# msxbreakout_fat.net
KiCad netlist of a schematic drawn in Altium Designer
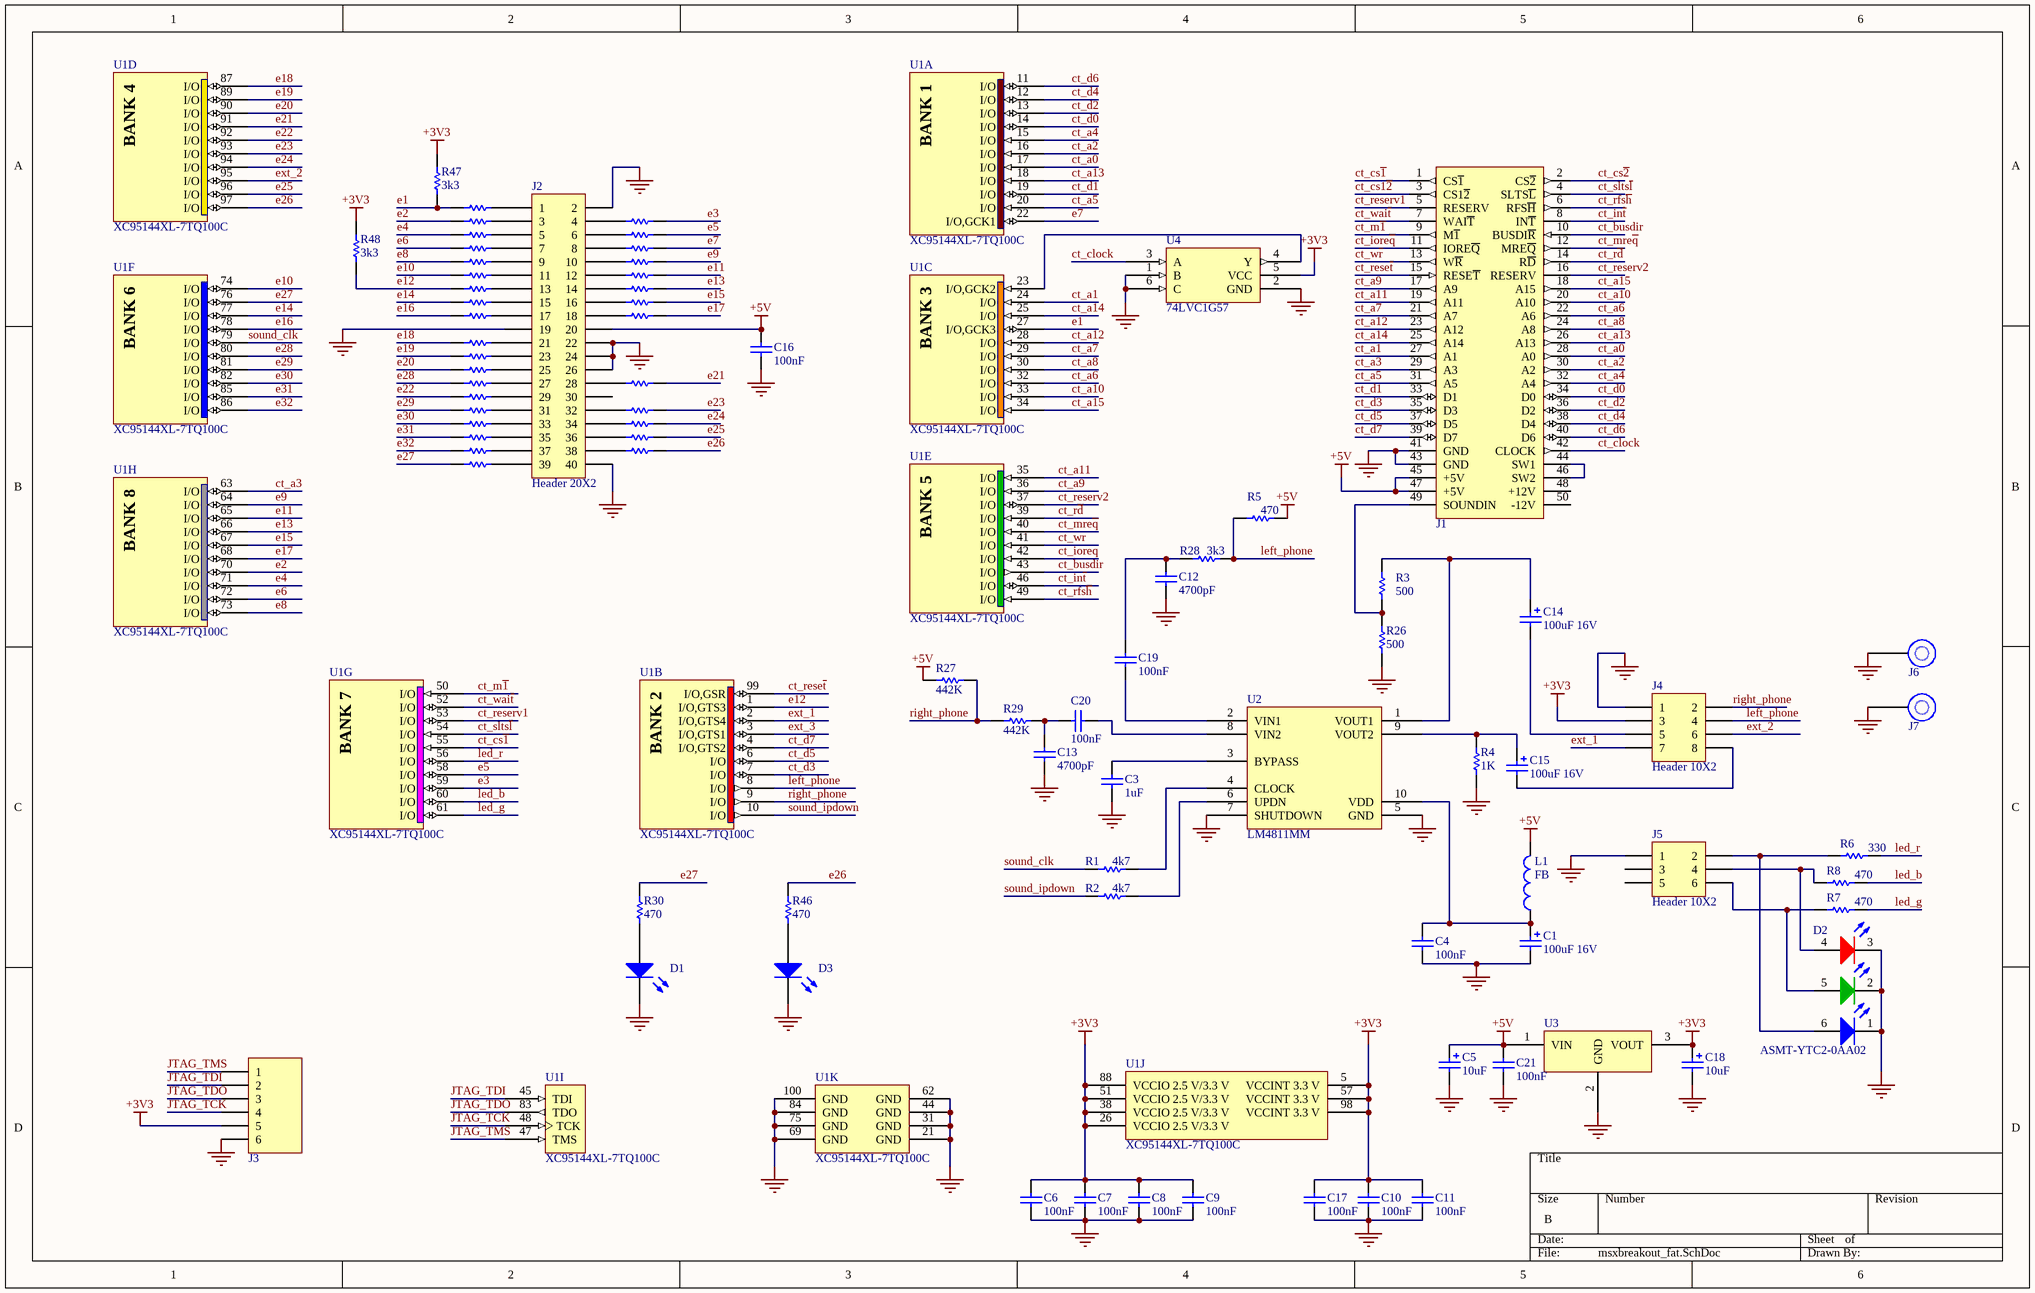
[diagram p0: msxbreakout_fat.SchDoc]

(export (version "E")
  (design (tool "Eeschema 10.0.6"))
  (components
    (comp (ref "C1")
      (value "100uF 16V")
      (footprint "cap1210POL")
      (description "Polarized Capacitor")
      (fields (field (name "Comment") "Cap Pol1") (field (name "PUBLISHER") "Altium Limited"))
      (libsource (lib "altium-import") (part "root_3_Cap Pol1_"))
    )
    (comp (ref "C3")
      (value "1uF")
      (footprint "cap0603")
      (description "Capacitor")
      (fields (field (name "Comment") "Cap") (field (name "PUBLISHER") "Altium Limited"))
      (libsource (lib "altium-import") (part "root_3_Cap_"))
    )
    (comp (ref "C4")
      (value "100nF")
      (footprint "cap0603")
      (description "Capacitor")
      (fields (field (name "Comment") "Cap") (field (name "PUBLISHER") "Altium Limited"))
      (libsource (lib "altium-import") (part "root_1_Cap_"))
    )
    (comp (ref "C5")
      (value "10uF")
      (footprint "cap1210POL")
      (description "Polarized Capacitor")
      (fields (field (name "Comment") "Cap Pol1") (field (name "PUBLISHER") "Altium Limited"))
      (libsource (lib "altium-import") (part "root_3_Cap Pol1_"))
    )
    (comp (ref "C6")
      (value "100nF")
      (footprint "cap0603")
      (description "Capacitor")
      (fields (field (name "Comment") "Cap") (field (name "PUBLISHER") "Altium Limited"))
      (libsource (lib "altium-import") (part "root_1_Cap_"))
    )
    (comp (ref "C7")
      (value "100nF")
      (footprint "cap0603")
      (description "Capacitor")
      (fields (field (name "Comment") "Cap") (field (name "PUBLISHER") "Altium Limited"))
      (libsource (lib "altium-import") (part "root_1_Cap_"))
    )
    (comp (ref "C8")
      (value "100nF")
      (footprint "cap0603")
      (description "Capacitor")
      (fields (field (name "Comment") "Cap") (field (name "PUBLISHER") "Altium Limited"))
      (libsource (lib "altium-import") (part "root_1_Cap_"))
    )
    (comp (ref "C9")
      (value "100nF")
      (footprint "cap0603")
      (description "Capacitor")
      (fields (field (name "Comment") "Cap") (field (name "PUBLISHER") "Altium Limited"))
      (libsource (lib "altium-import") (part "root_1_Cap_"))
    )
    (comp (ref "C10")
      (value "100nF")
      (footprint "cap0603")
      (description "Capacitor")
      (fields (field (name "Comment") "Cap") (field (name "PUBLISHER") "Altium Limited"))
      (libsource (lib "altium-import") (part "root_1_Cap_"))
    )
    (comp (ref "C11")
      (value "100nF")
      (footprint "cap0603")
      (description "Capacitor")
      (fields (field (name "Comment") "Cap") (field (name "PUBLISHER") "Altium Limited"))
      (libsource (lib "altium-import") (part "root_1_Cap_"))
    )
    (comp (ref "C12")
      (value "4700pF")
      (footprint "cap0603")
      (description "Capacitor")
      (fields (field (name "Comment") "Cap") (field (name "PUBLISHER") "Altium Limited"))
      (libsource (lib "altium-import") (part "root_3_Cap_"))
    )
    (comp (ref "C13")
      (value "4700pF")
      (footprint "cap0603")
      (description "Capacitor")
      (fields (field (name "Comment") "Cap") (field (name "PUBLISHER") "Altium Limited"))
      (libsource (lib "altium-import") (part "root_3_Cap_"))
    )
    (comp (ref "C14")
      (value "100uF 16V")
      (footprint "cap1210POL")
      (description "Polarized Capacitor")
      (fields (field (name "Comment") "Cap Pol1") (field (name "PUBLISHER") "Altium Limited"))
      (libsource (lib "altium-import") (part "root_3_Cap Pol1_"))
    )
    (comp (ref "C15")
      (value "100uF 16V")
      (footprint "cap1210POL")
      (description "Polarized Capacitor")
      (fields (field (name "Comment") "Cap Pol1") (field (name "PUBLISHER") "Altium Limited"))
      (libsource (lib "altium-import") (part "root_3_Cap Pol1_"))
    )
    (comp (ref "C16")
      (value "100nF")
      (footprint "cap0603")
      (description "Capacitor")
      (fields (field (name "Comment") "Cap") (field (name "PUBLISHER") "Altium Limited"))
      (libsource (lib "altium-import") (part "root_1_Cap_"))
    )
    (comp (ref "C17")
      (value "100nF")
      (footprint "cap0603")
      (description "Capacitor")
      (fields (field (name "Comment") "Cap") (field (name "PUBLISHER") "Altium Limited"))
      (libsource (lib "altium-import") (part "root_1_Cap_"))
    )
    (comp (ref "C18")
      (value "10uF")
      (footprint "cap1210POL")
      (description "Polarized Capacitor")
      (fields (field (name "Comment") "Cap Pol1") (field (name "PUBLISHER") "Altium Limited"))
      (libsource (lib "altium-import") (part "root_3_Cap Pol1_"))
    )
    (comp (ref "C19")
      (value "100nF")
      (footprint "cap0603")
      (description "Capacitor")
      (fields (field (name "Comment") "Cap") (field (name "PUBLISHER") "Altium Limited"))
      (libsource (lib "altium-import") (part "root_1_Cap_"))
    )
    (comp (ref "C20")
      (value "100nF")
      (footprint "cap0603")
      (description "Capacitor")
      (fields (field (name "Comment") "Cap") (field (name "PUBLISHER") "Altium Limited"))
      (libsource (lib "altium-import") (part "root_2_Cap_"))
    )
    (comp (ref "C21")
      (value "100nF")
      (footprint "cap0603")
      (description "Capacitor")
      (fields (field (name "Comment") "Cap") (field (name "PUBLISHER") "Altium Limited"))
      (libsource (lib "altium-import") (part "root_1_Cap_"))
    )
    (comp (ref "D1")
      (value "APA1606SURCK")
      (footprint "LED-0603_LAMP_BLUE")
      (description "1.6x0.6mm RIGHT ANGLE SMD CHIP LED LAMP, Hyper Red")
      (libsource (lib "altium-import") (part "root_3_APA1606SURCK_"))
    )
    (comp (ref "D2")
      (value "ASMT-YTC2-0AA02")
      (footprint "ASMT-YTC2-0AA02")
      (description "Typical RED, GREEN, YELLOW, AMBER GaAs LED")
      (fields (field (name "PUBLISHER") "Altium Limited"))
      (libsource (lib "altium-import") (part "root_0_ASMT-YTC2-0AA02_"))
    )
    (comp (ref "D3")
      (value "APA1606SURCK")
      (footprint "LED-0603_LAMP_RED")
      (description "1.6x0.6mm RIGHT ANGLE SMD CHIP LED LAMP, Hyper Red")
      (libsource (lib "altium-import") (part "root_3_APA1606SURCK_"))
    )
    (comp (ref "J1")
      (value "msxcart")
      (footprint "msxcart")
      (libsource (lib "altium-import") (part "root_0_msxcart_"))
    )
    (comp (ref "J2")
      (value "Header 20X2")
      (footprint "HDR2X20_90")
      (description "Header, 40-Pin, Dual row")
      (libsource (lib "altium-import") (part "root_0_Header 20X2_"))
    )
    (comp (ref "J3")
      (value "Header 1X6")
      (footprint "HDR1X6_90")
      (description "Header, 6-Pin, Single row")
      (libsource (lib "msxarm") (part "Header 1X6"))
    )
    (comp (ref "J4")
      (value "Header 10X2")
      (footprint "HDR2X4_90")
      (description "Header, 8 -Pin, Dual row")
      (libsource (lib "altium-import") (part "root_0_Header 4X2_"))
    )
    (comp (ref "J5")
      (value "Header 10X2")
      (footprint "HDR2X3_90")
      (description "Header, 10-Pin, Dual row")
      (libsource (lib "altium-import") (part "root_0_Header 3X2_"))
    )
    (comp (ref "J6")
      (value "MountHole")
      (footprint "MOUNTHOLE")
      (description "Mounting hole")
      (libsource (lib "altium-import") (part "root_0_MountHole_"))
    )
    (comp (ref "J7")
      (value "MountHole")
      (footprint "MOUNTHOLE")
      (description "Mounting hole")
      (libsource (lib "altium-import") (part "root_0_MountHole_"))
    )
    (comp (ref "L1")
      (value "FB")
      (footprint "ind1206")
      (description "Inductor")
      (fields (field (name "PUBLISHER") "Altium Limited"))
      (libsource (lib "altium-import") (part "root_1_Inductor_"))
    )
    (comp (ref "R1")
      (value "4k7")
      (footprint "res0603")
      (description "Resistor")
      (fields (field (name "Comment") "Res1") (field (name "PUBLISHER") "Altium Limited"))
      (libsource (lib "altium-import") (part "root_0_Res1_"))
    )
    (comp (ref "R2")
      (value "4k7")
      (footprint "res0603")
      (description "Resistor")
      (fields (field (name "Comment") "Res1") (field (name "PUBLISHER") "Altium Limited"))
      (libsource (lib "altium-import") (part "root_0_Res1_"))
    )
    (comp (ref "R3")
      (value "500")
      (footprint "res0603")
      (description "Resistor")
      (fields (field (name "Comment") "Res1") (field (name "PUBLISHER") "Altium Limited"))
      (libsource (lib "altium-import") (part "root_1_Res1_"))
    )
    (comp (ref "R4")
      (value "1K")
      (footprint "res0603")
      (description "Resistor")
      (fields (field (name "Comment") "Res1") (field (name "PUBLISHER") "Altium Limited"))
      (libsource (lib "altium-import") (part "root_1_Res1_"))
    )
    (comp (ref "R5")
      (value "470")
      (footprint "res0603")
      (description "Resistor")
      (fields (field (name "Comment") "Res1") (field (name "PUBLISHER") "Altium Limited"))
      (libsource (lib "altium-import") (part "root_0_Res1_"))
    )
    (comp (ref "R6")
      (value "330")
      (footprint "res0603")
      (description "Resistor")
      (fields (field (name "Comment") "Res1") (field (name "PUBLISHER") "Altium Limited"))
      (libsource (lib "altium-import") (part "root_0_Res1_"))
    )
    (comp (ref "R7")
      (value "470")
      (footprint "res0603")
      (description "Resistor")
      (fields (field (name "Comment") "Res1") (field (name "PUBLISHER") "Altium Limited"))
      (libsource (lib "altium-import") (part "root_0_Res1_"))
    )
    (comp (ref "R8")
      (value "470")
      (footprint "res0603")
      (description "Resistor")
      (fields (field (name "Comment") "Res1") (field (name "PUBLISHER") "Altium Limited"))
      (libsource (lib "altium-import") (part "root_0_Res1_"))
    )
    (comp (ref "R9")
      (value "Res1")
      (footprint "res0603")
      (description "Resistor")
      (fields (field (name "PUBLISHER") "Altium Limited"))
      (libsource (lib "altium-import") (part "root_0_Res1_"))
    )
    (comp (ref "R10")
      (value "Res1")
      (footprint "res0603")
      (description "Resistor")
      (fields (field (name "PUBLISHER") "Altium Limited"))
      (libsource (lib "altium-import") (part "root_0_Res1_"))
    )
    (comp (ref "R11")
      (value "Res1")
      (footprint "res0603")
      (description "Resistor")
      (fields (field (name "PUBLISHER") "Altium Limited"))
      (libsource (lib "altium-import") (part "root_0_Res1_"))
    )
    (comp (ref "R12")
      (value "Res1")
      (footprint "res0603")
      (description "Resistor")
      (fields (field (name "PUBLISHER") "Altium Limited"))
      (libsource (lib "altium-import") (part "root_0_Res1_"))
    )
    (comp (ref "R13")
      (value "Res1")
      (footprint "res0603")
      (description "Resistor")
      (fields (field (name "PUBLISHER") "Altium Limited"))
      (libsource (lib "altium-import") (part "root_0_Res1_"))
    )
    (comp (ref "R14")
      (value "Res1")
      (footprint "res0603")
      (description "Resistor")
      (fields (field (name "PUBLISHER") "Altium Limited"))
      (libsource (lib "altium-import") (part "root_0_Res1_"))
    )
    (comp (ref "R15")
      (value "Res1")
      (footprint "res0603")
      (description "Resistor")
      (fields (field (name "PUBLISHER") "Altium Limited"))
      (libsource (lib "altium-import") (part "root_0_Res1_"))
    )
    (comp (ref "R16")
      (value "Res1")
      (footprint "res0603")
      (description "Resistor")
      (fields (field (name "PUBLISHER") "Altium Limited"))
      (libsource (lib "altium-import") (part "root_0_Res1_"))
    )
    (comp (ref "R17")
      (value "Res1")
      (footprint "res0603")
      (description "Resistor")
      (fields (field (name "PUBLISHER") "Altium Limited"))
      (libsource (lib "altium-import") (part "root_0_Res1_"))
    )
    (comp (ref "R18")
      (value "Res1")
      (footprint "res0603")
      (description "Resistor")
      (fields (field (name "PUBLISHER") "Altium Limited"))
      (libsource (lib "altium-import") (part "root_0_Res1_"))
    )
    (comp (ref "R19")
      (value "Res1")
      (footprint "res0603")
      (description "Resistor")
      (fields (field (name "PUBLISHER") "Altium Limited"))
      (libsource (lib "altium-import") (part "root_0_Res1_"))
    )
    (comp (ref "R20")
      (value "Res1")
      (footprint "res0603")
      (description "Resistor")
      (fields (field (name "PUBLISHER") "Altium Limited"))
      (libsource (lib "altium-import") (part "root_0_Res1_"))
    )
    (comp (ref "R21")
      (value "Res1")
      (footprint "res0603")
      (description "Resistor")
      (fields (field (name "PUBLISHER") "Altium Limited"))
      (libsource (lib "altium-import") (part "root_0_Res1_"))
    )
    (comp (ref "R22")
      (value "Res1")
      (footprint "res0603")
      (description "Resistor")
      (fields (field (name "PUBLISHER") "Altium Limited"))
      (libsource (lib "altium-import") (part "root_0_Res1_"))
    )
    (comp (ref "R23")
      (value "Res1")
      (footprint "res0603")
      (description "Resistor")
      (fields (field (name "PUBLISHER") "Altium Limited"))
      (libsource (lib "altium-import") (part "root_0_Res1_"))
    )
    (comp (ref "R24")
      (value "Res1")
      (footprint "res0603")
      (description "Resistor")
      (fields (field (name "PUBLISHER") "Altium Limited"))
      (libsource (lib "altium-import") (part "root_0_Res1_"))
    )
    (comp (ref "R25")
      (value "Res1")
      (footprint "res0603")
      (description "Resistor")
      (fields (field (name "PUBLISHER") "Altium Limited"))
      (libsource (lib "altium-import") (part "root_0_Res1_"))
    )
    (comp (ref "R26")
      (value "500")
      (footprint "res0603")
      (description "Resistor")
      (fields (field (name "Comment") "Res1") (field (name "PUBLISHER") "Altium Limited"))
      (libsource (lib "altium-import") (part "root_1_Res1_"))
    )
    (comp (ref "R27")
      (value "442K")
      (footprint "res0603")
      (description "Resistor")
      (fields (field (name "PUBLISHER") "Altium Limited"))
      (libsource (lib "altium-import") (part "root_0_Resistor_"))
    )
    (comp (ref "R28")
      (value "3k3")
      (footprint "res0603")
      (description "Resistor")
      (fields (field (name "Comment") "Res1") (field (name "PUBLISHER") "Altium Limited"))
      (libsource (lib "altium-import") (part "root_0_Res1_"))
    )
    (comp (ref "R29")
      (value "442K")
      (footprint "res0603")
      (description "Resistor")
      (fields (field (name "PUBLISHER") "Altium Limited"))
      (libsource (lib "altium-import") (part "root_0_Resistor_"))
    )
    (comp (ref "R30")
      (value "470")
      (footprint "res0603")
      (description "Resistor")
      (fields (field (name "Comment") "Res1") (field (name "PUBLISHER") "Altium Limited"))
      (libsource (lib "altium-import") (part "root_1_Res1_"))
    )
    (comp (ref "R31")
      (value "Res1")
      (footprint "res0603")
      (description "Resistor")
      (fields (field (name "PUBLISHER") "Altium Limited"))
      (libsource (lib "altium-import") (part "root_0_Res1_"))
    )
    (comp (ref "R32")
      (value "Res1")
      (footprint "res0603")
      (description "Resistor")
      (fields (field (name "PUBLISHER") "Altium Limited"))
      (libsource (lib "altium-import") (part "root_0_Res1_"))
    )
    (comp (ref "R33")
      (value "Res1")
      (footprint "res0603")
      (description "Resistor")
      (fields (field (name "PUBLISHER") "Altium Limited"))
      (libsource (lib "altium-import") (part "root_0_Res1_"))
    )
    (comp (ref "R34")
      (value "Res1")
      (footprint "res0603")
      (description "Resistor")
      (fields (field (name "PUBLISHER") "Altium Limited"))
      (libsource (lib "altium-import") (part "root_0_Res1_"))
    )
    (comp (ref "R35")
      (value "Res1")
      (footprint "res0603")
      (description "Resistor")
      (fields (field (name "PUBLISHER") "Altium Limited"))
      (libsource (lib "altium-import") (part "root_0_Res1_"))
    )
    (comp (ref "R36")
      (value "Res1")
      (footprint "res0603")
      (description "Resistor")
      (fields (field (name "PUBLISHER") "Altium Limited"))
      (libsource (lib "altium-import") (part "root_0_Res1_"))
    )
    (comp (ref "R37")
      (value "Res1")
      (footprint "res0603")
      (description "Resistor")
      (fields (field (name "PUBLISHER") "Altium Limited"))
      (libsource (lib "altium-import") (part "root_0_Res1_"))
    )
    (comp (ref "R38")
      (value "Res1")
      (footprint "res0603")
      (description "Resistor")
      (fields (field (name "PUBLISHER") "Altium Limited"))
      (libsource (lib "altium-import") (part "root_0_Res1_"))
    )
    (comp (ref "R39")
      (value "Res1")
      (footprint "res0603")
      (description "Resistor")
      (fields (field (name "PUBLISHER") "Altium Limited"))
      (libsource (lib "altium-import") (part "root_0_Res1_"))
    )
    (comp (ref "R40")
      (value "Res1")
      (footprint "res0603")
      (description "Resistor")
      (fields (field (name "PUBLISHER") "Altium Limited"))
      (libsource (lib "altium-import") (part "root_0_Res1_"))
    )
    (comp (ref "R41")
      (value "Res1")
      (footprint "res0603")
      (description "Resistor")
      (fields (field (name "PUBLISHER") "Altium Limited"))
      (libsource (lib "altium-import") (part "root_0_Res1_"))
    )
    (comp (ref "R42")
      (value "Res1")
      (footprint "res0603")
      (description "Resistor")
      (fields (field (name "PUBLISHER") "Altium Limited"))
      (libsource (lib "altium-import") (part "root_0_Res1_"))
    )
    (comp (ref "R43")
      (value "Res1")
      (footprint "res0603")
      (description "Resistor")
      (fields (field (name "PUBLISHER") "Altium Limited"))
      (libsource (lib "altium-import") (part "root_0_Res1_"))
    )
    (comp (ref "R44")
      (value "Res1")
      (footprint "res0603")
      (description "Resistor")
      (fields (field (name "PUBLISHER") "Altium Limited"))
      (libsource (lib "altium-import") (part "root_0_Res1_"))
    )
    (comp (ref "R45")
      (value "Res1")
      (footprint "res0603")
      (description "Resistor")
      (fields (field (name "PUBLISHER") "Altium Limited"))
      (libsource (lib "altium-import") (part "root_0_Res1_"))
    )
    (comp (ref "R46")
      (value "470")
      (footprint "res0603")
      (description "Resistor")
      (fields (field (name "Comment") "Res1") (field (name "PUBLISHER") "Altium Limited"))
      (libsource (lib "altium-import") (part "root_1_Res1_"))
    )
    (comp (ref "R47")
      (value "3k3")
      (footprint "res0603")
      (description "Resistor")
      (fields (field (name "Comment") "Res1") (field (name "PUBLISHER") "Altium Limited"))
      (libsource (lib "altium-import") (part "root_1_Res1_"))
    )
    (comp (ref "R48")
      (value "3k3")
      (footprint "res0603")
      (description "Resistor")
      (fields (field (name "Comment") "Res1") (field (name "PUBLISHER") "Altium Limited"))
      (libsource (lib "altium-import") (part "root_1_Res1_"))
    )
    (comp (ref "U1")
      (value "XC95144XL-7TQ100C")
      (footprint "TQ100_M")
      (libsource (lib "altium-import") (part "root_0_XC95144XL-7TQ100C_"))
    )
    (comp (ref "U2") (value "LM4811MM") (footprint "LM4811MM") (libsource (lib "msxarm") (part "LM4811MM")))
    (comp (ref "U3")
      (value "Regulator 3V3")
      (footprint "sot223_4")
      (libsource (lib "altium-import") (part "root_0_Regulator 3V3_"))
    )
    (comp (ref "U4")
      (value "74LVC1G57")
      (footprint "SOT-363 PKG")
      (libsource (lib "altium-import") (part "root_0_74LVC1G57_"))
    )
  )
  (nets
    (net (code "1") (name "+3V3") (class "Default")
      (node (ref "C10") (pin "2") (pinfunction "2_2") (pintype "passive"))
      (node (ref "C11") (pin "2") (pinfunction "2_2") (pintype "passive"))
      (node (ref "C17") (pin "2") (pinfunction "2_2") (pintype "passive"))
      (node (ref "C18") (pin "1") (pinfunction "1_1") (pintype "passive"))
      (node (ref "C6") (pin "2") (pinfunction "2_2") (pintype "passive"))
      (node (ref "C7") (pin "2") (pinfunction "2_2") (pintype "passive"))
      (node (ref "C8") (pin "2") (pinfunction "2_2") (pintype "passive"))
      (node (ref "C9") (pin "2") (pinfunction "2_2") (pintype "passive"))
      (node (ref "J3") (pin "5") (pinfunction "5_5") (pintype "passive"))
      (node (ref "J4") (pin "3") (pinfunction "3_3") (pintype "passive"))
      (node (ref "R47") (pin "2") (pinfunction "2_2") (pintype "passive"))
      (node (ref "R48") (pin "2") (pinfunction "2_2") (pintype "passive"))
      (node (ref "U1") (pin "26") (pinfunction "VCCIO_2.5_V/3.3_V_26") (pintype "power_in"))
      (node (ref "U1") (pin "38") (pinfunction "VCCIO_2.5_V/3.3_V_38") (pintype "power_in"))
      (node (ref "U1") (pin "5") (pinfunction "VCCINT_3.3_V_5") (pintype "power_in"))
      (node (ref "U1") (pin "51") (pinfunction "VCCIO_2.5_V/3.3_V_51") (pintype "power_in"))
      (node (ref "U1") (pin "57") (pinfunction "VCCINT_3.3_V_57") (pintype "power_in"))
      (node (ref "U1") (pin "88") (pinfunction "VCCIO_2.5_V/3.3_V_88") (pintype "power_in"))
      (node (ref "U1") (pin "98") (pinfunction "VCCINT_3.3_V_98") (pintype "power_in"))
      (node (ref "U3") (pin "3") (pinfunction "VOUT_3") (pintype "passive"))
      (node (ref "U4") (pin "5") (pinfunction "VCC_5") (pintype "power_in"))
    )
    (net (code "2") (name "+5V") (class "Default")
      (node (ref "C16") (pin "2") (pinfunction "2_2") (pintype "passive"))
      (node (ref "C21") (pin "2") (pinfunction "2_2") (pintype "passive"))
      (node (ref "C5") (pin "1") (pinfunction "1_1") (pintype "passive"))
      (node (ref "J1") (pin "45") (pinfunction "+5V_45") (pintype "power_in"))
      (node (ref "J1") (pin "47") (pinfunction "+5V_47") (pintype "power_in"))
      (node (ref "J2") (pin "20") (pinfunction "20_20") (pintype "passive"))
      (node (ref "L1") (pin "2") (pinfunction "2_2") (pintype "passive"))
      (node (ref "R27") (pin "1") (pinfunction "1_1") (pintype "passive"))
      (node (ref "R5") (pin "2") (pinfunction "2_2") (pintype "passive"))
      (node (ref "U3") (pin "1") (pinfunction "VIN_1") (pintype "passive"))
    )
    (net (code "3") (name "/JTAG_TCK") (class "Default")
      (node (ref "J3") (pin "4") (pinfunction "4_4") (pintype "passive"))
      (node (ref "U1") (pin "48") (pinfunction "TCK_48") (pintype "input"))
    )
    (net (code "4") (name "/JTAG_TDI") (class "Default")
      (node (ref "J3") (pin "2") (pinfunction "2_2") (pintype "passive"))
      (node (ref "U1") (pin "45") (pinfunction "TDI_45") (pintype "input"))
    )
    (net (code "5") (name "/JTAG_TDO") (class "Default")
      (node (ref "J3") (pin "3") (pinfunction "3_3") (pintype "passive"))
      (node (ref "U1") (pin "83") (pinfunction "TDO_83") (pintype "output"))
    )
    (net (code "6") (name "/JTAG_TMS") (class "Default")
      (node (ref "J3") (pin "1") (pinfunction "1_1") (pintype "passive"))
      (node (ref "U1") (pin "47") (pinfunction "TMS_47") (pintype "input"))
    )
    (net (code "7") (name "/ct_a0") (class "Default")
      (node (ref "J1") (pin "28") (pinfunction "A0_28") (pintype "output"))
      (node (ref "U1") (pin "17") (pinfunction "I/O_17") (pintype "bidirectional"))
    )
    (net (code "8") (name "/ct_a1") (class "Default")
      (node (ref "J1") (pin "27") (pinfunction "A1_27") (pintype "output"))
      (node (ref "U1") (pin "24") (pinfunction "I/O_24") (pintype "bidirectional"))
    )
    (net (code "9") (name "/ct_a2") (class "Default")
      (node (ref "J1") (pin "30") (pinfunction "A2_30") (pintype "output"))
      (node (ref "U1") (pin "16") (pinfunction "I/O_16") (pintype "bidirectional"))
    )
    (net (code "10") (name "/ct_a3") (class "Default")
      (node (ref "J1") (pin "29") (pinfunction "A3_29") (pintype "output"))
      (node (ref "U1") (pin "63") (pinfunction "I/O_63") (pintype "bidirectional"))
    )
    (net (code "11") (name "/ct_a4") (class "Default")
      (node (ref "J1") (pin "32") (pinfunction "A4_32") (pintype "output"))
      (node (ref "U1") (pin "15") (pinfunction "I/O_15") (pintype "bidirectional"))
    )
    (net (code "12") (name "/ct_a5") (class "Default")
      (node (ref "J1") (pin "31") (pinfunction "A5_31") (pintype "output"))
      (node (ref "U1") (pin "20") (pinfunction "I/O_20") (pintype "bidirectional"))
    )
    (net (code "13") (name "/ct_a6") (class "Default")
      (node (ref "J1") (pin "22") (pinfunction "A6_22") (pintype "output"))
      (node (ref "U1") (pin "32") (pinfunction "I/O_32") (pintype "bidirectional"))
    )
    (net (code "14") (name "/ct_a7") (class "Default")
      (node (ref "J1") (pin "21") (pinfunction "A7_21") (pintype "output"))
      (node (ref "U1") (pin "29") (pinfunction "I/O_29") (pintype "bidirectional"))
    )
    (net (code "15") (name "/ct_a8") (class "Default")
      (node (ref "J1") (pin "24") (pinfunction "A8_24") (pintype "output"))
      (node (ref "U1") (pin "30") (pinfunction "I/O_30") (pintype "bidirectional"))
    )
    (net (code "16") (name "/ct_a9") (class "Default")
      (node (ref "J1") (pin "17") (pinfunction "A9_17") (pintype "output"))
      (node (ref "U1") (pin "36") (pinfunction "I/O_36") (pintype "bidirectional"))
    )
    (net (code "17") (name "/ct_a10") (class "Default")
      (node (ref "J1") (pin "20") (pinfunction "A10_20") (pintype "output"))
      (node (ref "U1") (pin "33") (pinfunction "I/O_33") (pintype "bidirectional"))
    )
    (net (code "18") (name "/ct_a11") (class "Default")
      (node (ref "J1") (pin "19") (pinfunction "A11_19") (pintype "output"))
      (node (ref "U1") (pin "35") (pinfunction "I/O_35") (pintype "bidirectional"))
    )
    (net (code "19") (name "/ct_a12") (class "Default")
      (node (ref "J1") (pin "23") (pinfunction "A12_23") (pintype "output"))
      (node (ref "U1") (pin "28") (pinfunction "I/O_28") (pintype "bidirectional"))
    )
    (net (code "20") (name "/ct_a13") (class "Default")
      (node (ref "J1") (pin "26") (pinfunction "A13_26") (pintype "output"))
      (node (ref "U1") (pin "18") (pinfunction "I/O_18") (pintype "bidirectional"))
    )
    (net (code "21") (name "/ct_a14") (class "Default")
      (node (ref "J1") (pin "25") (pinfunction "A14_25") (pintype "output"))
      (node (ref "U1") (pin "25") (pinfunction "I/O_25") (pintype "bidirectional"))
    )
    (net (code "22") (name "/ct_a15") (class "Default")
      (node (ref "J1") (pin "18") (pinfunction "A15_18") (pintype "output"))
      (node (ref "U1") (pin "34") (pinfunction "I/O_34") (pintype "bidirectional"))
    )
    (net (code "23") (name "/ct_busdir") (class "Default")
      (node (ref "J1") (pin "10") (pinfunction "BUSDI~{R}_10") (pintype "input"))
      (node (ref "U1") (pin "43") (pinfunction "I/O_43") (pintype "bidirectional"))
    )
    (net (code "24") (name "/ct_clock") (class "Default")
      (node (ref "J1") (pin "42") (pinfunction "CLOCK_42") (pintype "output"))
      (node (ref "U4") (pin "3") (pinfunction "A_3") (pintype "input"))
    )
    (net (code "25") (name "/ct_cs1~{2}") (class "Default")
      (node (ref "J1") (pin "3") (pinfunction "CS1~{2}_3") (pintype "output"))
    )
    (net (code "26") (name "/ct_cs~{1}") (class "Default")
      (node (ref "J1") (pin "1") (pinfunction "CS~{1}_1") (pintype "output"))
      (node (ref "U1") (pin "55") (pinfunction "I/O_55") (pintype "bidirectional"))
    )
    (net (code "27") (name "/ct_cs~{2}") (class "Default")
      (node (ref "J1") (pin "2") (pinfunction "CS~{2}_2") (pintype "output"))
    )
    (net (code "28") (name "/ct_d0") (class "Default")
      (node (ref "J1") (pin "34") (pinfunction "D0_34") (pintype "bidirectional"))
      (node (ref "U1") (pin "14") (pinfunction "I/O_14") (pintype "bidirectional"))
    )
    (net (code "29") (name "/ct_d1") (class "Default")
      (node (ref "J1") (pin "33") (pinfunction "D1_33") (pintype "bidirectional"))
      (node (ref "U1") (pin "19") (pinfunction "I/O_19") (pintype "bidirectional"))
    )
    (net (code "30") (name "/ct_d2") (class "Default")
      (node (ref "J1") (pin "36") (pinfunction "D2_36") (pintype "bidirectional"))
      (node (ref "U1") (pin "13") (pinfunction "I/O_13") (pintype "bidirectional"))
    )
    (net (code "31") (name "/ct_d3") (class "Default")
      (node (ref "J1") (pin "35") (pinfunction "D3_35") (pintype "bidirectional"))
      (node (ref "U1") (pin "7") (pinfunction "I/O_7") (pintype "bidirectional"))
    )
    (net (code "32") (name "/ct_d4") (class "Default")
      (node (ref "J1") (pin "38") (pinfunction "D4_38") (pintype "bidirectional"))
      (node (ref "U1") (pin "12") (pinfunction "I/O_12") (pintype "bidirectional"))
    )
    (net (code "33") (name "/ct_d5") (class "Default")
      (node (ref "J1") (pin "37") (pinfunction "D5_37") (pintype "bidirectional"))
      (node (ref "U1") (pin "6") (pinfunction "I/O_6") (pintype "bidirectional"))
    )
    (net (code "34") (name "/ct_d6") (class "Default")
      (node (ref "J1") (pin "40") (pinfunction "D6_40") (pintype "bidirectional"))
      (node (ref "U1") (pin "11") (pinfunction "I/O_11") (pintype "bidirectional"))
    )
    (net (code "35") (name "/ct_d7") (class "Default")
      (node (ref "J1") (pin "39") (pinfunction "D7_39") (pintype "bidirectional"))
      (node (ref "U1") (pin "4") (pinfunction "I/O,GTS2_4") (pintype "bidirectional"))
    )
    (net (code "36") (name "/ct_in~{t}") (class "Default")
      (node (ref "J1") (pin "8") (pinfunction "IN~{T}_8") (pintype "open_collector"))
      (node (ref "U1") (pin "46") (pinfunction "I/O_46") (pintype "bidirectional"))
    )
    (net (code "37") (name "/ct_iore~{q}") (class "Default")
      (node (ref "J1") (pin "11") (pinfunction "IORE~{Q}_11") (pintype "output"))
      (node (ref "U1") (pin "42") (pinfunction "I/O_42") (pintype "bidirectional"))
    )
    (net (code "38") (name "/ct_mre~{q}") (class "Default")
      (node (ref "J1") (pin "12") (pinfunction "MRE~{Q}_12") (pintype "output"))
      (node (ref "U1") (pin "40") (pinfunction "I/O_40") (pintype "bidirectional"))
    )
    (net (code "39") (name "/ct_m~{1}") (class "Default")
      (node (ref "J1") (pin "9") (pinfunction "M~{1}_9") (pintype "output"))
      (node (ref "U1") (pin "50") (pinfunction "I/O_50") (pintype "bidirectional"))
    )
    (net (code "40") (name "/ct_reserv1") (class "Default")
      (node (ref "J1") (pin "5") (pinfunction "RESERV_5") (pintype "tri_state"))
      (node (ref "U1") (pin "53") (pinfunction "I/O_53") (pintype "bidirectional"))
    )
    (net (code "41") (name "/ct_reserv2") (class "Default")
      (node (ref "J1") (pin "16") (pinfunction "RESERV_16") (pintype "passive"))
      (node (ref "U1") (pin "37") (pinfunction "I/O_37") (pintype "bidirectional"))
    )
    (net (code "42") (name "/ct_rese~{t}") (class "Default")
      (node (ref "J1") (pin "15") (pinfunction "RESE~{T}_15") (pintype "input"))
      (node (ref "U1") (pin "99") (pinfunction "I/O,GSR_99") (pintype "bidirectional"))
    )
    (net (code "43") (name "/ct_rfs~{h}") (class "Default")
      (node (ref "J1") (pin "6") (pinfunction "RFS~{H}_6") (pintype "output"))
      (node (ref "U1") (pin "49") (pinfunction "I/O_49") (pintype "bidirectional"))
    )
    (net (code "44") (name "/ct_r~{d}") (class "Default")
      (node (ref "J1") (pin "14") (pinfunction "R~{D}_14") (pintype "output"))
      (node (ref "U1") (pin "39") (pinfunction "I/O_39") (pintype "bidirectional"))
    )
    (net (code "45") (name "/ct_slts~{l}") (class "Default")
      (node (ref "J1") (pin "4") (pinfunction "SLTS~{L}_4") (pintype "output"))
      (node (ref "U1") (pin "54") (pinfunction "I/O_54") (pintype "bidirectional"))
    )
    (net (code "46") (name "/ct_wai~{t}") (class "Default")
      (node (ref "J1") (pin "7") (pinfunction "WAI~{T}_7") (pintype "open_collector"))
      (node (ref "U1") (pin "52") (pinfunction "I/O_52") (pintype "bidirectional"))
    )
    (net (code "47") (name "/ct_w~{r}") (class "Default")
      (node (ref "J1") (pin "13") (pinfunction "W~{R}_13") (pintype "output"))
      (node (ref "U1") (pin "41") (pinfunction "I/O_41") (pintype "bidirectional"))
    )
    (net (code "48") (name "/e1") (class "Default")
      (node (ref "R47") (pin "1") (pinfunction "1_1") (pintype "passive"))
      (node (ref "R9") (pin "1") (pinfunction "1_1") (pintype "passive"))
      (node (ref "U1") (pin "27") (pinfunction "I/O,GCK3_27") (pintype "bidirectional"))
    )
    (net (code "49") (name "/e2") (class "Default")
      (node (ref "R11") (pin "1") (pinfunction "1_1") (pintype "passive"))
      (node (ref "U1") (pin "70") (pinfunction "I/O_70") (pintype "bidirectional"))
    )
    (net (code "50") (name "/e3") (class "Default")
      (node (ref "R10") (pin "2") (pinfunction "2_2") (pintype "passive"))
      (node (ref "U1") (pin "59") (pinfunction "I/O_59") (pintype "bidirectional"))
    )
    (net (code "51") (name "/e4") (class "Default")
      (node (ref "R13") (pin "1") (pinfunction "1_1") (pintype "passive"))
      (node (ref "U1") (pin "71") (pinfunction "I/O_71") (pintype "bidirectional"))
    )
    (net (code "52") (name "/e5") (class "Default")
      (node (ref "R12") (pin "2") (pinfunction "2_2") (pintype "passive"))
      (node (ref "U1") (pin "58") (pinfunction "I/O_58") (pintype "bidirectional"))
    )
    (net (code "53") (name "/e6") (class "Default")
      (node (ref "R15") (pin "1") (pinfunction "1_1") (pintype "passive"))
      (node (ref "U1") (pin "72") (pinfunction "I/O_72") (pintype "bidirectional"))
    )
    (net (code "54") (name "/e7") (class "Default")
      (node (ref "R14") (pin "2") (pinfunction "2_2") (pintype "passive"))
      (node (ref "U1") (pin "22") (pinfunction "I/O,GCK1_22") (pintype "bidirectional"))
    )
    (net (code "55") (name "/e8") (class "Default")
      (node (ref "R18") (pin "1") (pinfunction "1_1") (pintype "passive"))
      (node (ref "U1") (pin "73") (pinfunction "I/O_73") (pintype "bidirectional"))
    )
    (net (code "56") (name "/e9") (class "Default")
      (node (ref "R16") (pin "2") (pinfunction "2_2") (pintype "passive"))
      (node (ref "U1") (pin "64") (pinfunction "I/O_64") (pintype "bidirectional"))
    )
    (net (code "57") (name "/e10") (class "Default")
      (node (ref "R20") (pin "1") (pinfunction "1_1") (pintype "passive"))
      (node (ref "U1") (pin "74") (pinfunction "I/O_74") (pintype "bidirectional"))
    )
    (net (code "58") (name "/e11") (class "Default")
      (node (ref "R17") (pin "2") (pinfunction "2_2") (pintype "passive"))
      (node (ref "U1") (pin "65") (pinfunction "I/O_65") (pintype "bidirectional"))
    )
    (net (code "59") (name "/e12") (class "Default")
      (node (ref "R22") (pin "1") (pinfunction "1_1") (pintype "passive"))
      (node (ref "R48") (pin "1") (pinfunction "1_1") (pintype "passive"))
      (node (ref "U1") (pin "1") (pinfunction "I/O,GTS3_1") (pintype "bidirectional"))
    )
    (net (code "60") (name "/e13") (class "Default")
      (node (ref "R19") (pin "2") (pinfunction "2_2") (pintype "passive"))
      (node (ref "U1") (pin "66") (pinfunction "I/O_66") (pintype "bidirectional"))
    )
    (net (code "61") (name "/e14") (class "Default")
      (node (ref "R24") (pin "1") (pinfunction "1_1") (pintype "passive"))
      (node (ref "U1") (pin "77") (pinfunction "I/O_77") (pintype "bidirectional"))
    )
    (net (code "62") (name "/e15") (class "Default")
      (node (ref "R21") (pin "2") (pinfunction "2_2") (pintype "passive"))
      (node (ref "U1") (pin "67") (pinfunction "I/O_67") (pintype "bidirectional"))
    )
    (net (code "63") (name "/e16") (class "Default")
      (node (ref "R25") (pin "1") (pinfunction "1_1") (pintype "passive"))
      (node (ref "U1") (pin "78") (pinfunction "I/O_78") (pintype "bidirectional"))
    )
    (net (code "64") (name "/e17") (class "Default")
      (node (ref "R23") (pin "2") (pinfunction "2_2") (pintype "passive"))
      (node (ref "U1") (pin "68") (pinfunction "I/O_68") (pintype "bidirectional"))
    )
    (net (code "65") (name "/e18") (class "Default")
      (node (ref "R31") (pin "1") (pinfunction "1_1") (pintype "passive"))
      (node (ref "U1") (pin "87") (pinfunction "I/O_87") (pintype "bidirectional"))
    )
    (net (code "66") (name "/e19") (class "Default")
      (node (ref "R32") (pin "1") (pinfunction "1_1") (pintype "passive"))
      (node (ref "U1") (pin "89") (pinfunction "I/O_89") (pintype "bidirectional"))
    )
    (net (code "67") (name "/e20") (class "Default")
      (node (ref "R33") (pin "1") (pinfunction "1_1") (pintype "passive"))
      (node (ref "U1") (pin "90") (pinfunction "I/O_90") (pintype "bidirectional"))
    )
    (net (code "68") (name "/e21") (class "Default")
      (node (ref "R34") (pin "2") (pinfunction "2_2") (pintype "passive"))
      (node (ref "U1") (pin "91") (pinfunction "I/O_91") (pintype "bidirectional"))
    )
    (net (code "69") (name "/e22") (class "Default")
      (node (ref "R36") (pin "1") (pinfunction "1_1") (pintype "passive"))
      (node (ref "U1") (pin "92") (pinfunction "I/O_92") (pintype "bidirectional"))
    )
    (net (code "70") (name "/e23") (class "Default")
      (node (ref "R39") (pin "2") (pinfunction "2_2") (pintype "passive"))
      (node (ref "U1") (pin "93") (pinfunction "I/O_93") (pintype "bidirectional"))
    )
    (net (code "71") (name "/e24") (class "Default")
      (node (ref "R37") (pin "2") (pinfunction "2_2") (pintype "passive"))
      (node (ref "U1") (pin "94") (pinfunction "I/O_94") (pintype "bidirectional"))
    )
    (net (code "72") (name "/e25") (class "Default")
      (node (ref "R41") (pin "2") (pinfunction "2_2") (pintype "passive"))
      (node (ref "U1") (pin "96") (pinfunction "I/O_96") (pintype "bidirectional"))
    )
    (net (code "73") (name "/e26") (class "Default")
      (node (ref "R43") (pin "2") (pinfunction "2_2") (pintype "passive"))
      (node (ref "R46") (pin "2") (pinfunction "2_2") (pintype "passive"))
      (node (ref "U1") (pin "97") (pinfunction "I/O_97") (pintype "bidirectional"))
    )
    (net (code "74") (name "/e27") (class "Default")
      (node (ref "R30") (pin "2") (pinfunction "2_2") (pintype "passive"))
      (node (ref "R45") (pin "1") (pinfunction "1_1") (pintype "passive"))
      (node (ref "U1") (pin "76") (pinfunction "I/O_76") (pintype "bidirectional"))
    )
    (net (code "75") (name "/e28") (class "Default")
      (node (ref "R35") (pin "1") (pinfunction "1_1") (pintype "passive"))
      (node (ref "U1") (pin "80") (pinfunction "I/O_80") (pintype "bidirectional"))
    )
    (net (code "76") (name "/e29") (class "Default")
      (node (ref "R38") (pin "1") (pinfunction "1_1") (pintype "passive"))
      (node (ref "U1") (pin "81") (pinfunction "I/O_81") (pintype "bidirectional"))
    )
    (net (code "77") (name "/e30") (class "Default")
      (node (ref "R40") (pin "1") (pinfunction "1_1") (pintype "passive"))
      (node (ref "U1") (pin "82") (pinfunction "I/O_82") (pintype "bidirectional"))
    )
    (net (code "78") (name "/e31") (class "Default")
      (node (ref "R42") (pin "1") (pinfunction "1_1") (pintype "passive"))
      (node (ref "U1") (pin "85") (pinfunction "I/O_85") (pintype "bidirectional"))
    )
    (net (code "79") (name "/e32") (class "Default")
      (node (ref "R44") (pin "1") (pinfunction "1_1") (pintype "passive"))
      (node (ref "U1") (pin "86") (pinfunction "I/O_86") (pintype "bidirectional"))
    )
    (net (code "80") (name "/ext_1") (class "Default")
      (node (ref "J4") (pin "7") (pinfunction "7_7") (pintype "passive"))
      (node (ref "U1") (pin "2") (pinfunction "I/O,GTS4_2") (pintype "bidirectional"))
    )
    (net (code "81") (name "/ext_2") (class "Default")
      (node (ref "J4") (pin "6") (pinfunction "6_6") (pintype "passive"))
      (node (ref "U1") (pin "95") (pinfunction "I/O_95") (pintype "bidirectional"))
    )
    (net (code "82") (name "/ext_3") (class "Default")
      (node (ref "U1") (pin "3") (pinfunction "I/O,GTS1_3") (pintype "bidirectional"))
    )
    (net (code "83") (name "/led_b") (class "Default")
      (node (ref "R8") (pin "2") (pinfunction "2_2") (pintype "passive"))
      (node (ref "U1") (pin "60") (pinfunction "I/O_60") (pintype "bidirectional"))
    )
    (net (code "84") (name "/led_g") (class "Default")
      (node (ref "R7") (pin "2") (pinfunction "2_2") (pintype "passive"))
      (node (ref "U1") (pin "61") (pinfunction "I/O_61") (pintype "bidirectional"))
    )
    (net (code "85") (name "/led_r") (class "Default")
      (node (ref "R6") (pin "2") (pinfunction "2_2") (pintype "passive"))
      (node (ref "U1") (pin "56") (pinfunction "I/O_56") (pintype "bidirectional"))
    )
    (net (code "86") (name "/left_phone") (class "Default")
      (node (ref "J4") (pin "4") (pinfunction "4_4") (pintype "passive"))
      (node (ref "R28") (pin "2") (pinfunction "2_2") (pintype "passive"))
      (node (ref "R5") (pin "1") (pinfunction "1_1") (pintype "passive"))
      (node (ref "U1") (pin "8") (pinfunction "I/O_8") (pintype "bidirectional"))
    )
    (net (code "87") (name "/right_phone") (class "Default")
      (node (ref "J4") (pin "2") (pinfunction "2_2") (pintype "passive"))
      (node (ref "R27") (pin "2") (pinfunction "2_2") (pintype "passive"))
      (node (ref "R29") (pin "1") (pinfunction "1_1") (pintype "passive"))
      (node (ref "U1") (pin "9") (pinfunction "I/O_9") (pintype "bidirectional"))
    )
    (net (code "88") (name "/sound_clk") (class "Default")
      (node (ref "R1") (pin "1") (pinfunction "1_1") (pintype "passive"))
      (node (ref "U1") (pin "79") (pinfunction "I/O_79") (pintype "bidirectional"))
    )
    (net (code "89") (name "/sound_ipdown") (class "Default")
      (node (ref "R2") (pin "1") (pinfunction "1_1") (pintype "passive"))
      (node (ref "U1") (pin "10") (pinfunction "I/O_10") (pintype "bidirectional"))
    )
    (net (code "90") (name "GND") (class "Default")
      (node (ref "C1") (pin "2") (pinfunction "2_2") (pintype "passive"))
      (node (ref "C10") (pin "1") (pinfunction "1_1") (pintype "passive"))
      (node (ref "C11") (pin "1") (pinfunction "1_1") (pintype "passive"))
      (node (ref "C12") (pin "2") (pinfunction "2_2") (pintype "passive"))
      (node (ref "C13") (pin "2") (pinfunction "2_2") (pintype "passive"))
      (node (ref "C16") (pin "1") (pinfunction "1_1") (pintype "passive"))
      (node (ref "C17") (pin "1") (pinfunction "1_1") (pintype "passive"))
      (node (ref "C18") (pin "2") (pinfunction "2_2") (pintype "passive"))
      (node (ref "C21") (pin "1") (pinfunction "1_1") (pintype "passive"))
      (node (ref "C3") (pin "2") (pinfunction "2_2") (pintype "passive"))
      (node (ref "C4") (pin "1") (pinfunction "1_1") (pintype "passive"))
      (node (ref "C5") (pin "2") (pinfunction "2_2") (pintype "passive"))
      (node (ref "C6") (pin "1") (pinfunction "1_1") (pintype "passive"))
      (node (ref "C7") (pin "1") (pinfunction "1_1") (pintype "passive"))
      (node (ref "C8") (pin "1") (pinfunction "1_1") (pintype "passive"))
      (node (ref "C9") (pin "1") (pinfunction "1_1") (pintype "passive"))
      (node (ref "D1") (pin "2") (pinfunction "K_2") (pintype "passive"))
      (node (ref "D2") (pin "1") (pinfunction "1_1") (pintype "passive"))
      (node (ref "D2") (pin "2") (pinfunction "2_2") (pintype "passive"))
      (node (ref "D2") (pin "3") (pinfunction "3_3") (pintype "passive"))
      (node (ref "D3") (pin "2") (pinfunction "K_2") (pintype "passive"))
      (node (ref "J1") (pin "41") (pinfunction "GND_41") (pintype "power_in"))
      (node (ref "J1") (pin "43") (pinfunction "GND_43") (pintype "power_in"))
      (node (ref "J2") (pin "19") (pinfunction "19_19") (pintype "passive"))
      (node (ref "J2") (pin "2") (pinfunction "2_2") (pintype "passive"))
      (node (ref "J2") (pin "22") (pinfunction "22_22") (pintype "passive"))
      (node (ref "J2") (pin "24") (pinfunction "24_24") (pintype "passive"))
      (node (ref "J2") (pin "26") (pinfunction "26_26") (pintype "passive"))
      (node (ref "J2") (pin "40") (pinfunction "40_40") (pintype "passive"))
      (node (ref "J3") (pin "6") (pinfunction "6_6") (pintype "passive"))
      (node (ref "J4") (pin "1") (pinfunction "1_1") (pintype "passive"))
      (node (ref "J5") (pin "1") (pinfunction "1_1") (pintype "passive"))
      (node (ref "J6") (pin "1") (pinfunction "1_1") (pintype "passive"))
      (node (ref "J7") (pin "1") (pinfunction "1_1") (pintype "passive"))
      (node (ref "R26") (pin "1") (pinfunction "1_1") (pintype "passive"))
      (node (ref "R4") (pin "1") (pinfunction "1_1") (pintype "passive"))
      (node (ref "U1") (pin "100") (pinfunction "GND_100") (pintype "power_in"))
      (node (ref "U1") (pin "21") (pinfunction "GND_21") (pintype "power_in"))
      (node (ref "U1") (pin "31") (pinfunction "GND_31") (pintype "power_in"))
      (node (ref "U1") (pin "44") (pinfunction "GND_44") (pintype "power_in"))
      (node (ref "U1") (pin "62") (pinfunction "GND_62") (pintype "power_in"))
      (node (ref "U1") (pin "69") (pinfunction "GND_69") (pintype "power_in"))
      (node (ref "U1") (pin "75") (pinfunction "GND_75") (pintype "power_in"))
      (node (ref "U1") (pin "84") (pinfunction "GND_84") (pintype "power_in"))
      (node (ref "U2") (pin "5") (pinfunction "GND_5") (pintype "passive"))
      (node (ref "U2") (pin "7") (pinfunction "SHUTDOWN_7") (pintype "passive"))
      (node (ref "U3") (pin "2") (pinfunction "GND_2") (pintype "passive"))
      (node (ref "U4") (pin "1") (pinfunction "B_1") (pintype "input"))
      (node (ref "U4") (pin "2") (pinfunction "GND_2") (pintype "power_in"))
      (node (ref "U4") (pin "6") (pinfunction "C_6") (pintype "input"))
    )
    (net (code "91") (name "Net-(C12-Pad1)") (class "Default")
      (node (ref "C12") (pin "1") (pinfunction "1_1") (pintype "passive"))
      (node (ref "C19") (pin "2") (pinfunction "2_2") (pintype "passive"))
      (node (ref "R28") (pin "1") (pinfunction "1_1") (pintype "passive"))
    )
    (net (code "92") (name "Net-(C13-Pad1)") (class "Default")
      (node (ref "C13") (pin "1") (pinfunction "1_1") (pintype "passive"))
      (node (ref "C20") (pin "2") (pinfunction "2_2") (pintype "passive"))
      (node (ref "R29") (pin "2") (pinfunction "2_2") (pintype "passive"))
    )
    (net (code "93") (name "Net-(C14-Pad2)") (class "Default")
      (node (ref "C14") (pin "2") (pinfunction "2_2") (pintype "passive"))
      (node (ref "J4") (pin "5") (pinfunction "5_5") (pintype "passive"))
    )
    (net (code "94") (name "Net-(C15-Pad2)") (class "Default")
      (node (ref "C15") (pin "2") (pinfunction "2_2") (pintype "passive"))
      (node (ref "J4") (pin "8") (pinfunction "8_8") (pintype "passive"))
    )
    (net (code "95") (name "Net-(D1-A)") (class "Default")
      (node (ref "D1") (pin "1") (pinfunction "A_1") (pintype "passive"))
      (node (ref "R30") (pin "1") (pinfunction "1_1") (pintype "passive"))
    )
    (net (code "96") (name "Net-(D2-Pad4)") (class "Default")
      (node (ref "D2") (pin "4") (pinfunction "4_4") (pintype "passive"))
      (node (ref "J5") (pin "4") (pinfunction "4_4") (pintype "passive"))
      (node (ref "R8") (pin "1") (pinfunction "1_1") (pintype "passive"))
    )
    (net (code "97") (name "Net-(D2-Pad5)") (class "Default")
      (node (ref "D2") (pin "5") (pinfunction "5_5") (pintype "passive"))
      (node (ref "J5") (pin "6") (pinfunction "6_6") (pintype "passive"))
      (node (ref "R7") (pin "1") (pinfunction "1_1") (pintype "passive"))
    )
    (net (code "98") (name "Net-(D2-Pad6)") (class "Default")
      (node (ref "D2") (pin "6") (pinfunction "6_6") (pintype "passive"))
      (node (ref "J5") (pin "2") (pinfunction "2_2") (pintype "passive"))
      (node (ref "R6") (pin "1") (pinfunction "1_1") (pintype "passive"))
    )
    (net (code "99") (name "Net-(D3-A)") (class "Default")
      (node (ref "D3") (pin "1") (pinfunction "A_1") (pintype "passive"))
      (node (ref "R46") (pin "1") (pinfunction "1_1") (pintype "passive"))
    )
    (net (code "100") (name "Net-(J1-SOUNDIN)") (class "Default")
      (node (ref "J1") (pin "49") (pinfunction "SOUNDIN_49") (pintype "passive"))
      (node (ref "R26") (pin "2") (pinfunction "2_2") (pintype "passive"))
      (node (ref "R3") (pin "1") (pinfunction "1_1") (pintype "passive"))
    )
    (net (code "101") (name "Net-(J1-SW1)") (class "Default")
      (node (ref "J1") (pin "44") (pinfunction "SW1_44") (pintype "passive"))
      (node (ref "J1") (pin "46") (pinfunction "SW2_46") (pintype "passive"))
    )
    (net (code "102") (name "Net-(J2-Pad1)") (class "Default")
      (node (ref "J2") (pin "1") (pinfunction "1_1") (pintype "passive"))
      (node (ref "R9") (pin "2") (pinfunction "2_2") (pintype "passive"))
    )
    (net (code "103") (name "Net-(J2-Pad3)") (class "Default")
      (node (ref "J2") (pin "3") (pinfunction "3_3") (pintype "passive"))
      (node (ref "R11") (pin "2") (pinfunction "2_2") (pintype "passive"))
    )
    (net (code "104") (name "Net-(J2-Pad4)") (class "Default")
      (node (ref "J2") (pin "4") (pinfunction "4_4") (pintype "passive"))
      (node (ref "R10") (pin "1") (pinfunction "1_1") (pintype "passive"))
    )
    (net (code "105") (name "Net-(J2-Pad5)") (class "Default")
      (node (ref "J2") (pin "5") (pinfunction "5_5") (pintype "passive"))
      (node (ref "R13") (pin "2") (pinfunction "2_2") (pintype "passive"))
    )
    (net (code "106") (name "Net-(J2-Pad6)") (class "Default")
      (node (ref "J2") (pin "6") (pinfunction "6_6") (pintype "passive"))
      (node (ref "R12") (pin "1") (pinfunction "1_1") (pintype "passive"))
    )
    (net (code "107") (name "Net-(J2-Pad7)") (class "Default")
      (node (ref "J2") (pin "7") (pinfunction "7_7") (pintype "passive"))
      (node (ref "R15") (pin "2") (pinfunction "2_2") (pintype "passive"))
    )
    (net (code "108") (name "Net-(J2-Pad8)") (class "Default")
      (node (ref "J2") (pin "8") (pinfunction "8_8") (pintype "passive"))
      (node (ref "R14") (pin "1") (pinfunction "1_1") (pintype "passive"))
    )
    (net (code "109") (name "Net-(J2-Pad9)") (class "Default")
      (node (ref "J2") (pin "9") (pinfunction "9_9") (pintype "passive"))
      (node (ref "R18") (pin "2") (pinfunction "2_2") (pintype "passive"))
    )
    (net (code "110") (name "Net-(J2-Pad10)") (class "Default")
      (node (ref "J2") (pin "10") (pinfunction "10_10") (pintype "passive"))
      (node (ref "R16") (pin "1") (pinfunction "1_1") (pintype "passive"))
    )
    (net (code "111") (name "Net-(J2-Pad11)") (class "Default")
      (node (ref "J2") (pin "11") (pinfunction "11_11") (pintype "passive"))
      (node (ref "R20") (pin "2") (pinfunction "2_2") (pintype "passive"))
    )
    (net (code "112") (name "Net-(J2-Pad12)") (class "Default")
      (node (ref "J2") (pin "12") (pinfunction "12_12") (pintype "passive"))
      (node (ref "R17") (pin "1") (pinfunction "1_1") (pintype "passive"))
    )
    (net (code "113") (name "Net-(J2-Pad13)") (class "Default")
      (node (ref "J2") (pin "13") (pinfunction "13_13") (pintype "passive"))
      (node (ref "R22") (pin "2") (pinfunction "2_2") (pintype "passive"))
    )
    (net (code "114") (name "Net-(J2-Pad14)") (class "Default")
      (node (ref "J2") (pin "14") (pinfunction "14_14") (pintype "passive"))
      (node (ref "R19") (pin "1") (pinfunction "1_1") (pintype "passive"))
    )
    (net (code "115") (name "Net-(J2-Pad15)") (class "Default")
      (node (ref "J2") (pin "15") (pinfunction "15_15") (pintype "passive"))
      (node (ref "R24") (pin "2") (pinfunction "2_2") (pintype "passive"))
    )
    (net (code "116") (name "Net-(J2-Pad16)") (class "Default")
      (node (ref "J2") (pin "16") (pinfunction "16_16") (pintype "passive"))
      (node (ref "R21") (pin "1") (pinfunction "1_1") (pintype "passive"))
    )
    (net (code "117") (name "Net-(J2-Pad17)") (class "Default")
      (node (ref "J2") (pin "17") (pinfunction "17_17") (pintype "passive"))
      (node (ref "R25") (pin "2") (pinfunction "2_2") (pintype "passive"))
    )
    (net (code "118") (name "Net-(J2-Pad18)") (class "Default")
      (node (ref "J2") (pin "18") (pinfunction "18_18") (pintype "passive"))
      (node (ref "R23") (pin "1") (pinfunction "1_1") (pintype "passive"))
    )
    (net (code "119") (name "Net-(J2-Pad21)") (class "Default")
      (node (ref "J2") (pin "21") (pinfunction "21_21") (pintype "passive"))
      (node (ref "R31") (pin "2") (pinfunction "2_2") (pintype "passive"))
    )
    (net (code "120") (name "Net-(J2-Pad23)") (class "Default")
      (node (ref "J2") (pin "23") (pinfunction "23_23") (pintype "passive"))
      (node (ref "R32") (pin "2") (pinfunction "2_2") (pintype "passive"))
    )
    (net (code "121") (name "Net-(J2-Pad25)") (class "Default")
      (node (ref "J2") (pin "25") (pinfunction "25_25") (pintype "passive"))
      (node (ref "R33") (pin "2") (pinfunction "2_2") (pintype "passive"))
    )
    (net (code "122") (name "Net-(J2-Pad27)") (class "Default")
      (node (ref "J2") (pin "27") (pinfunction "27_27") (pintype "passive"))
      (node (ref "R35") (pin "2") (pinfunction "2_2") (pintype "passive"))
    )
    (net (code "123") (name "Net-(J2-Pad28)") (class "Default")
      (node (ref "J2") (pin "28") (pinfunction "28_28") (pintype "passive"))
      (node (ref "R34") (pin "1") (pinfunction "1_1") (pintype "passive"))
    )
    (net (code "124") (name "Net-(J2-Pad29)") (class "Default")
      (node (ref "J2") (pin "29") (pinfunction "29_29") (pintype "passive"))
      (node (ref "R36") (pin "2") (pinfunction "2_2") (pintype "passive"))
    )
    (net (code "125") (name "Net-(J2-Pad31)") (class "Default")
      (node (ref "J2") (pin "31") (pinfunction "31_31") (pintype "passive"))
      (node (ref "R38") (pin "2") (pinfunction "2_2") (pintype "passive"))
    )
    (net (code "126") (name "Net-(J2-Pad32)") (class "Default")
      (node (ref "J2") (pin "32") (pinfunction "32_32") (pintype "passive"))
      (node (ref "R39") (pin "1") (pinfunction "1_1") (pintype "passive"))
    )
    (net (code "127") (name "Net-(J2-Pad33)") (class "Default")
      (node (ref "J2") (pin "33") (pinfunction "33_33") (pintype "passive"))
      (node (ref "R40") (pin "2") (pinfunction "2_2") (pintype "passive"))
    )
    (net (code "128") (name "Net-(J2-Pad34)") (class "Default")
      (node (ref "J2") (pin "34") (pinfunction "34_34") (pintype "passive"))
      (node (ref "R37") (pin "1") (pinfunction "1_1") (pintype "passive"))
    )
    (net (code "129") (name "Net-(J2-Pad35)") (class "Default")
      (node (ref "J2") (pin "35") (pinfunction "35_35") (pintype "passive"))
      (node (ref "R42") (pin "2") (pinfunction "2_2") (pintype "passive"))
    )
    (net (code "130") (name "Net-(J2-Pad36)") (class "Default")
      (node (ref "J2") (pin "36") (pinfunction "36_36") (pintype "passive"))
      (node (ref "R41") (pin "1") (pinfunction "1_1") (pintype "passive"))
    )
    (net (code "131") (name "Net-(J2-Pad37)") (class "Default")
      (node (ref "J2") (pin "37") (pinfunction "37_37") (pintype "passive"))
      (node (ref "R44") (pin "2") (pinfunction "2_2") (pintype "passive"))
    )
    (net (code "132") (name "Net-(J2-Pad38)") (class "Default")
      (node (ref "J2") (pin "38") (pinfunction "38_38") (pintype "passive"))
      (node (ref "R43") (pin "1") (pinfunction "1_1") (pintype "passive"))
    )
    (net (code "133") (name "Net-(J2-Pad39)") (class "Default")
      (node (ref "J2") (pin "39") (pinfunction "39_39") (pintype "passive"))
      (node (ref "R45") (pin "2") (pinfunction "2_2") (pintype "passive"))
    )
    (net (code "134") (name "Net-(U1C-I{slash}O,GCK2)") (class "Default")
      (node (ref "U1") (pin "23") (pinfunction "I/O,GCK2_23") (pintype "bidirectional"))
      (node (ref "U4") (pin "4") (pinfunction "Y_4") (pintype "output"))
    )
    (net (code "135") (name "Net-(U2-BYPASS)") (class "Default")
      (node (ref "C3") (pin "1") (pinfunction "1_1") (pintype "passive"))
      (node (ref "U2") (pin "3") (pinfunction "BYPASS_3") (pintype "passive"))
    )
    (net (code "136") (name "Net-(U2-CLOCK)") (class "Default")
      (node (ref "R1") (pin "2") (pinfunction "2_2") (pintype "passive"))
      (node (ref "U2") (pin "4") (pinfunction "CLOCK_4") (pintype "passive"))
    )
    (net (code "137") (name "Net-(U2-UPDN)") (class "Default")
      (node (ref "R2") (pin "2") (pinfunction "2_2") (pintype "passive"))
      (node (ref "U2") (pin "6") (pinfunction "UPDN_6") (pintype "passive"))
    )
    (net (code "138") (name "Net-(U2-VDD)") (class "Default")
      (node (ref "C1") (pin "1") (pinfunction "1_1") (pintype "passive"))
      (node (ref "C4") (pin "2") (pinfunction "2_2") (pintype "passive"))
      (node (ref "L1") (pin "1") (pinfunction "1_1") (pintype "passive"))
      (node (ref "U2") (pin "10") (pinfunction "VDD_10") (pintype "passive"))
    )
    (net (code "139") (name "Net-(U2-VIN1)") (class "Default")
      (node (ref "C19") (pin "1") (pinfunction "1_1") (pintype "passive"))
      (node (ref "U2") (pin "2") (pinfunction "VIN1_2") (pintype "passive"))
    )
    (net (code "140") (name "Net-(U2-VIN2)") (class "Default")
      (node (ref "C20") (pin "1") (pinfunction "1_1") (pintype "passive"))
      (node (ref "U2") (pin "8") (pinfunction "VIN2_8") (pintype "passive"))
    )
    (net (code "141") (name "Net-(U2-VOUT1)") (class "Default")
      (node (ref "C14") (pin "1") (pinfunction "1_1") (pintype "passive"))
      (node (ref "R3") (pin "2") (pinfunction "2_2") (pintype "passive"))
      (node (ref "U2") (pin "1") (pinfunction "VOUT1_1") (pintype "passive"))
    )
    (net (code "142") (name "Net-(U2-VOUT2)") (class "Default")
      (node (ref "C15") (pin "1") (pinfunction "1_1") (pintype "passive"))
      (node (ref "R4") (pin "2") (pinfunction "2_2") (pintype "passive"))
      (node (ref "U2") (pin "9") (pinfunction "VOUT2_9") (pintype "passive"))
    )
    (net (code "143") (name "unconnected-(J1-+12V-Pad48)") (class "Default")
      (node (ref "J1") (pin "48") (pinfunction "+12V_48") (pintype "power_in"))
    )
    (net (code "144") (name "unconnected-(J1--12V-Pad50)") (class "Default")
      (node (ref "J1") (pin "50") (pinfunction "-12V_50") (pintype "power_in"))
    )
    (net (code "145") (name "unconnected-(J2-Pad30)") (class "Default")
      (node (ref "J2") (pin "30") (pinfunction "30_30") (pintype "passive"))
    )
    (net (code "146") (name "unconnected-(J5-Pad3)") (class "Default")
      (node (ref "J5") (pin "3") (pinfunction "3_3") (pintype "passive"))
    )
    (net (code "147") (name "unconnected-(J5-Pad5)") (class "Default")
      (node (ref "J5") (pin "5") (pinfunction "5_5") (pintype "passive"))
    )
  )
)
